# sim7600CE.net
KiCad netlist of a schematic drawn in Altium Designer
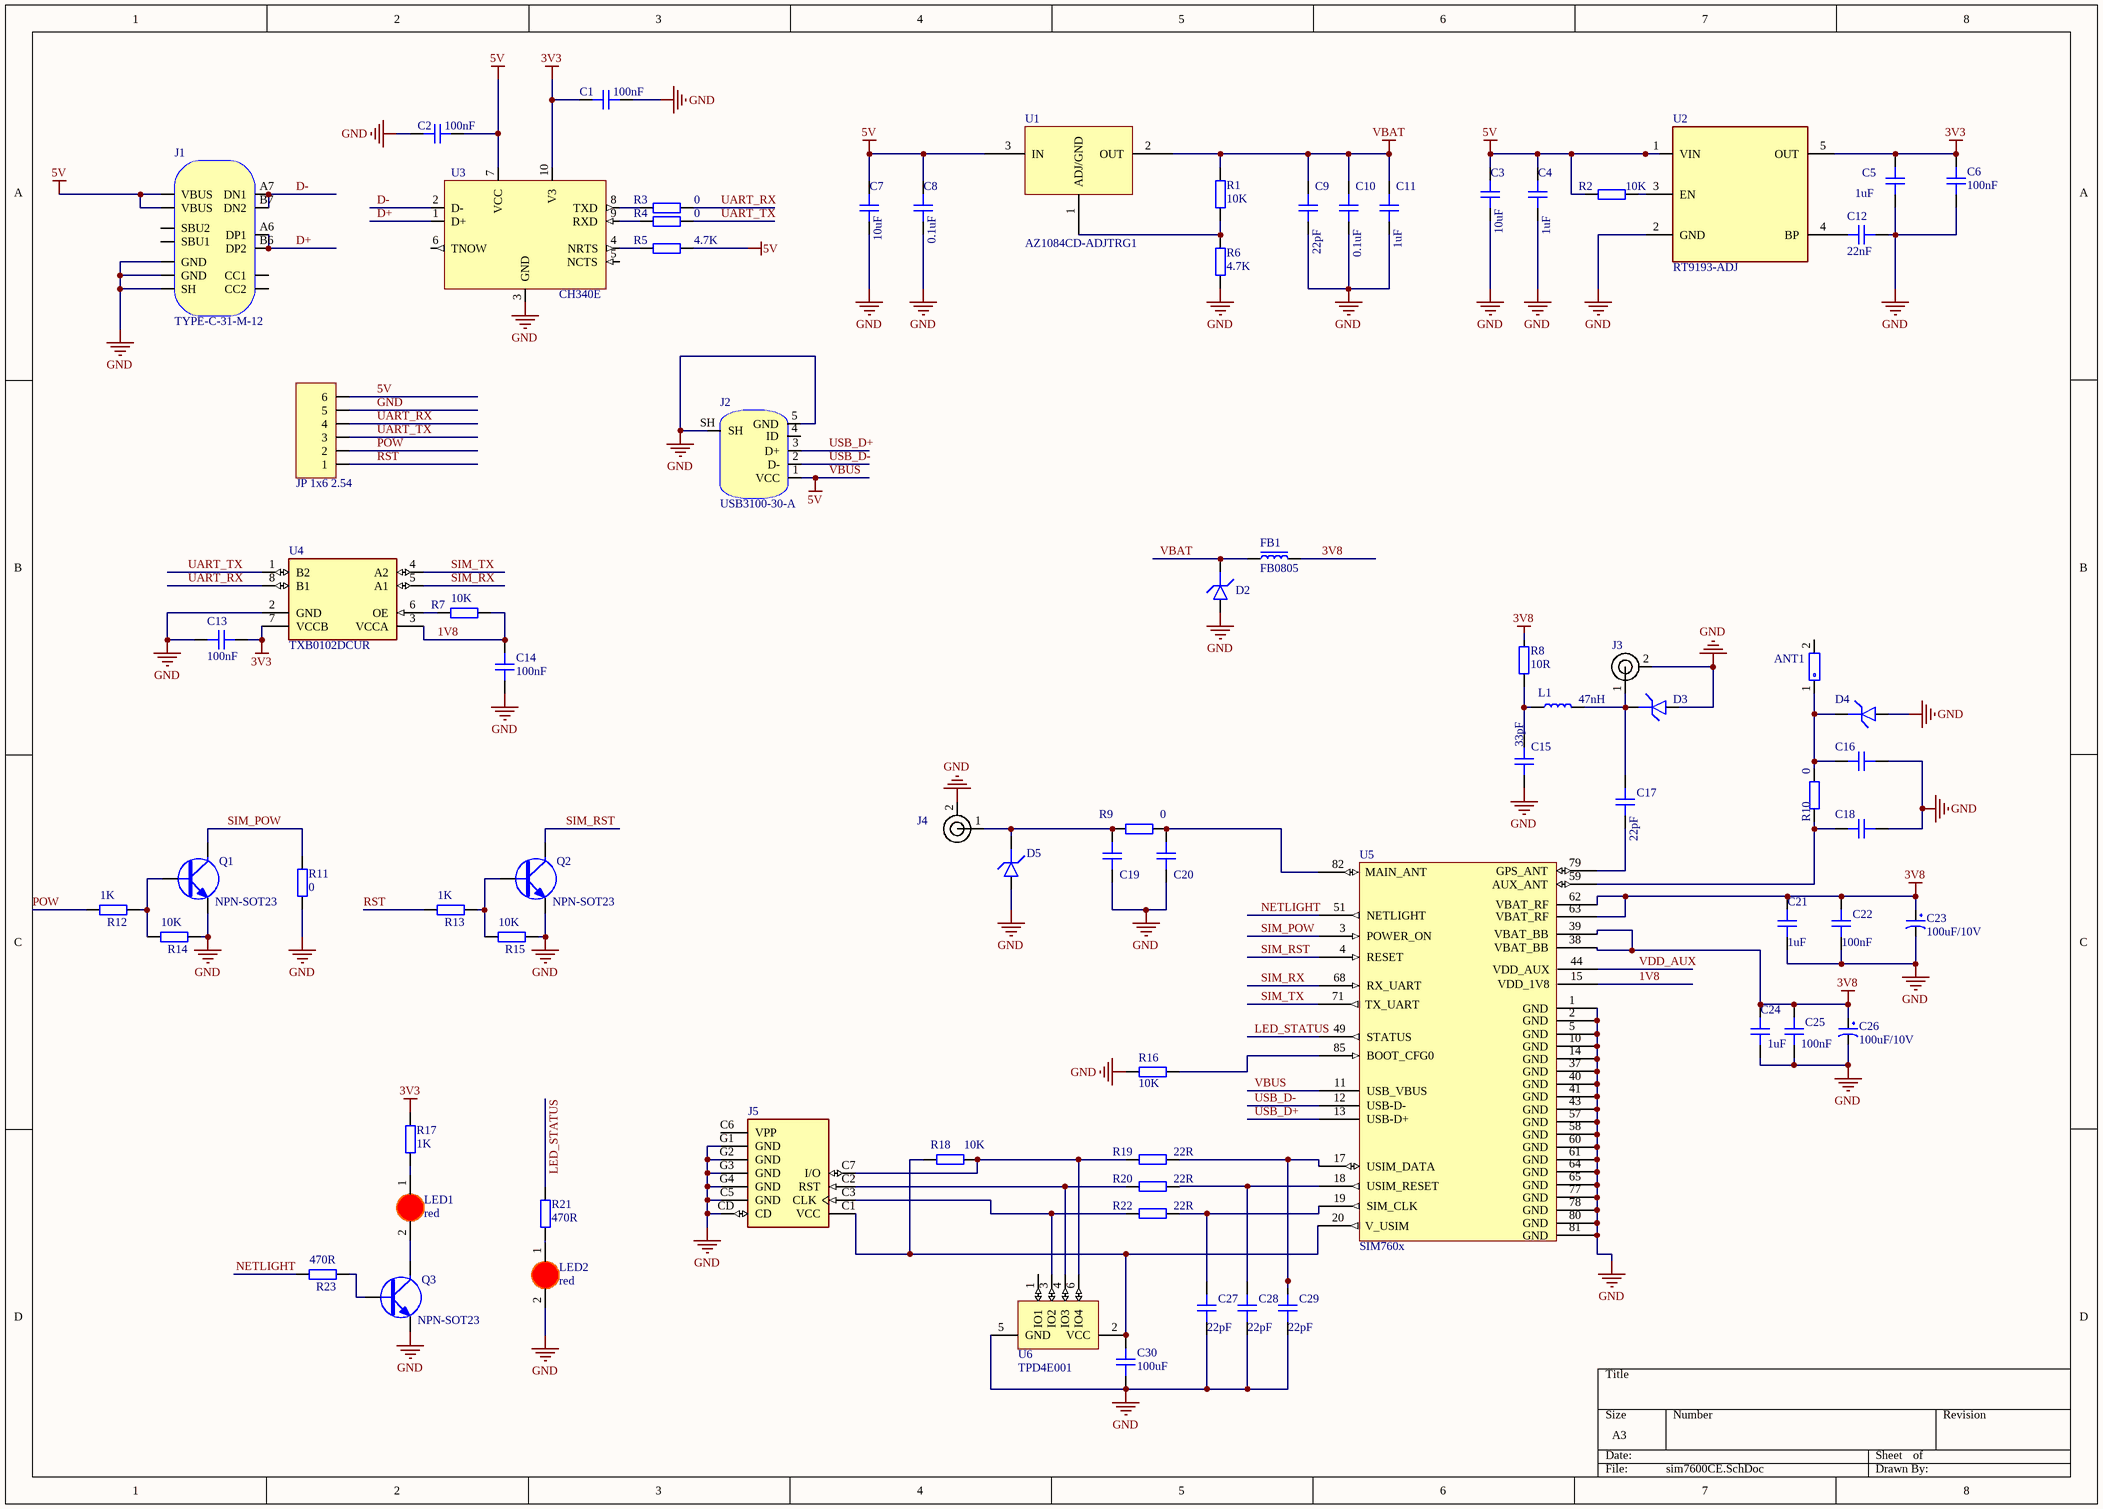
[diagram p0: sim7600CE.SchDoc]

(export (version "E")
  (design (tool "Eeschema 10.0.6"))
  (components
    (comp (ref "ANT1")
      (value "ANT MAIN")
      (footprint "AMCA92-2R660G-S1F-T")
      (libsource (lib "bethu") (part "AMCA92-2R660G-S1F-T"))
    )
    (comp (ref "C1")
      (value "100nF")
      (footprint "CAP_0603")
      (description "Capacitor SMD 0603")
      (libsource (lib "bethu") (part "CAP_0603"))
    )
    (comp (ref "C2")
      (value "100nF")
      (footprint "CAP_0603")
      (description "Capacitor SMD 0603")
      (libsource (lib "bethu") (part "CAP_0603"))
    )
    (comp (ref "C3")
      (value "10uF")
      (footprint "CAP_0603")
      (description "Capacitor SMD 0603")
      (libsource (lib "bethu") (part "CAP_0603"))
    )
    (comp (ref "C4")
      (value "1uF")
      (footprint "CAP_0603")
      (description "Capacitor SMD 0603")
      (libsource (lib "bethu") (part "CAP_0603"))
    )
    (comp (ref "C5")
      (value "1uF")
      (footprint "CAP_0603")
      (description "Capacitor SMD 0603")
      (libsource (lib "bethu") (part "CAP_0603"))
    )
    (comp (ref "C6")
      (value "100nF")
      (footprint "CAP_0603")
      (description "Capacitor SMD 0603")
      (libsource (lib "bethu") (part "CAP_0603"))
    )
    (comp (ref "C7")
      (value "10uF")
      (footprint "CAP_0603")
      (description "Capacitor SMD 0603")
      (libsource (lib "bethu") (part "CAP_0603"))
    )
    (comp (ref "C8")
      (value "0.1uF")
      (footprint "CAP_0603")
      (description "Capacitor SMD 0603")
      (libsource (lib "bethu") (part "CAP_0603"))
    )
    (comp (ref "C9")
      (value "22pF")
      (footprint "CAP_0603")
      (description "Capacitor SMD 0603")
      (libsource (lib "bethu") (part "CAP_0603"))
    )
    (comp (ref "C10")
      (value "0.1uF")
      (footprint "CAP_0603")
      (description "Capacitor SMD 0603")
      (libsource (lib "bethu") (part "CAP_0603"))
    )
    (comp (ref "C11")
      (value "1uF")
      (footprint "CAP_0603")
      (description "Capacitor SMD 0603")
      (libsource (lib "bethu") (part "CAP_0603"))
    )
    (comp (ref "C12")
      (value "22nF")
      (footprint "CAP_0603")
      (description "Capacitor SMD 0603")
      (libsource (lib "bethu") (part "CAP_0603"))
    )
    (comp (ref "C13")
      (value "100nF")
      (footprint "CAP_0603")
      (description "Capacitor SMD 0603")
      (libsource (lib "bethu") (part "CAP_0603"))
    )
    (comp (ref "C14")
      (value "100nF")
      (footprint "CAP_0603")
      (description "Capacitor SMD 0603")
      (libsource (lib "bethu") (part "CAP_0603"))
    )
    (comp (ref "C15")
      (value "33pF")
      (footprint "CAP_0603")
      (description "Capacitor SMD 0603")
      (libsource (lib "bethu") (part "CAP_0603"))
    )
    (comp (ref "C16")
      (value "C0603")
      (footprint "CAP_0603")
      (description "Capacitor SMD 0603")
      (libsource (lib "bethu") (part "CAP_0603"))
    )
    (comp (ref "C17")
      (value "22pF")
      (footprint "CAP_0603")
      (description "Capacitor SMD 0603")
      (libsource (lib "bethu") (part "CAP_0603"))
    )
    (comp (ref "C18")
      (value "C0603")
      (footprint "CAP_0603")
      (description "Capacitor SMD 0603")
      (libsource (lib "bethu") (part "CAP_0603"))
    )
    (comp (ref "C19")
      (value "C0603")
      (footprint "CAP_0603")
      (description "Capacitor SMD 0603")
      (libsource (lib "bethu") (part "CAP_0603"))
    )
    (comp (ref "C20")
      (value "C0603")
      (footprint "CAP_0603")
      (description "Capacitor SMD 0603")
      (libsource (lib "bethu") (part "CAP_0603"))
    )
    (comp (ref "C21")
      (value "1uF")
      (footprint "CAP_0603")
      (description "Capacitor SMD 0603")
      (libsource (lib "bethu") (part "CAP_0603"))
    )
    (comp (ref "C22")
      (value "100nF")
      (footprint "CAP_0603")
      (description "Capacitor SMD 0603")
      (libsource (lib "bethu") (part "CAP_0603"))
    )
    (comp (ref "C23")
      (value "100uF/10V")
      (footprint "tu tantalum smd3216")
      (description "Tụ tantalum 7343 477C 16V 470uF 7.3x4.3mm")
      (libsource (lib "bethu") (part "CAP 477C"))
    )
    (comp (ref "C24")
      (value "1uF")
      (footprint "CAP_0603")
      (description "Capacitor SMD 0603")
      (libsource (lib "bethu") (part "CAP_0603"))
    )
    (comp (ref "C25")
      (value "100nF")
      (footprint "CAP_0603")
      (description "Capacitor SMD 0603")
      (libsource (lib "bethu") (part "CAP_0603"))
    )
    (comp (ref "C26")
      (value "100uF/10V")
      (footprint "tu tantalum smd3216")
      (description "Tụ tantalum 7343 477C 16V 470uF 7.3x4.3mm")
      (libsource (lib "bethu") (part "CAP 477C"))
    )
    (comp (ref "C27")
      (value "22pF")
      (footprint "CAP_0603")
      (description "Capacitor SMD 0603")
      (libsource (lib "bethu") (part "CAP_0603"))
    )
    (comp (ref "C28")
      (value "22pF")
      (footprint "CAP_0603")
      (description "Capacitor SMD 0603")
      (libsource (lib "bethu") (part "CAP_0603"))
    )
    (comp (ref "C29")
      (value "22pF")
      (footprint "CAP_0603")
      (description "Capacitor SMD 0603")
      (libsource (lib "bethu") (part "CAP_0603"))
    )
    (comp (ref "C30")
      (value "100uF")
      (footprint "CAP_0603")
      (description "Capacitor SMD 0603")
      (libsource (lib "bethu") (part "CAP_0603"))
    )
    (comp (ref "D2")
      (value "D_TVS_0402")
      (footprint "D_0402")
      (description "Diode TVS / ESD 0402")
      (libsource (lib "bethu") (part "D_TVS_0402"))
    )
    (comp (ref "D3")
      (value "D_TVS_0402")
      (footprint "D_0402")
      (description "Diode TVS / ESD 0402")
      (libsource (lib "bethu") (part "D_TVS_0402"))
    )
    (comp (ref "D4")
      (value "D_TVS_0402")
      (footprint "D_0402")
      (description "Diode TVS / ESD 0402")
      (libsource (lib "bethu") (part "D_TVS_0402"))
    )
    (comp (ref "D5")
      (value "D_TVS_0402")
      (footprint "D_0402")
      (description "Diode TVS / ESD 0402")
      (libsource (lib "bethu") (part "D_TVS_0402"))
    )
    (comp (ref "FB1")
      (value "FB0805")
      (footprint "FB_0805")
      (description "Ferrite Bead SMD 0805")
      (libsource (lib "bethu") (part "FB_0805"))
    )
    (comp (ref "J1")
      (value "TYPE-C-31-M-12")
      (footprint "TYPE-C-31-M-12")
      (description "USB Type C Connector Horizontal SMT")
      (fields (field (name "MANUFACTURER") "Koren Hroparts"))
      (libsource (lib "bethu") (part "TYPE-C-31-M-12"))
    )
    (comp (ref "J2")
      (value "USB3100-30-A")
      (footprint "USB3100-30-A")
      (description "USB Connector Type Micro B 2.0 SMD Reverse Mount")
      (fields (field (name "MANUFACTURER") "GCT"))
      (libsource (lib "bethu") (part "USB3100-30-A"))
    )
    (comp (ref "J3")
      (value "U.FL-R-SMT-1(60)")
      (footprint "U.FL-R-SMT-1(60)")
      (description "RF Connector u.FL 50 Ohms 6 GHz")
      (fields (field (name "MANUFACTURER") "Hirose Connector"))
      (libsource (lib "bethu") (part "ANT-SMD"))
    )
    (comp (ref "J4")
      (value "U.FL-R-SMT-1(60)")
      (footprint "U.FL-R-SMT-1(60)")
      (description "RF Connector u.FL 50 Ohms 6 GHz")
      (fields (field (name "MANUFACTURER") "Hirose Connector"))
      (libsource (lib "bethu") (part "ANT-SMD"))
    )
    (comp (ref "J5")
      (value "SIM8066-6-1-14-01-A_REVA")
      (footprint "GCT_SIM8066-6-1-14-01-A_REVA")
      (description "Nano SIM Card ConnectorPush-Push Type, SMT, 6Pin, 1.44mm Profile")
      (libsource (lib "bethu") (part "SIM8066-6-1-14-01-A_REVA"))
    )
    (comp (ref "JP1")
      (value "JP 1x6 2.54")
      (footprint "HDR1X6")
      (description "Cắm")
      (libsource (lib "bethu") (part "JP 1x6 2.54 Duc Thang"))
    )
    (comp (ref "L1")
      (value "47nH")
      (footprint "IND_0603")
      (description "Inductor SMD 0603")
      (libsource (lib "bethu") (part "IND_0603"))
    )
    (comp (ref "LED1")
      (value "red")
      (footprint "LED-0805-Red")
      (libsource (lib "bethu") (part "LED_0805_RED"))
    )
    (comp (ref "LED2")
      (value "red")
      (footprint "LED-0805-Red")
      (libsource (lib "bethu") (part "LED_0805_RED"))
    )
    (comp (ref "Q1")
      (value "NPN-SOT23")
      (footprint "SOT23 - 3PIN")
      (libsource (lib "bethu") (part "NPN-SOT23"))
    )
    (comp (ref "Q2")
      (value "NPN-SOT23")
      (footprint "SOT23 - 3PIN")
      (libsource (lib "bethu") (part "NPN-SOT23"))
    )
    (comp (ref "Q3")
      (value "NPN-SOT23")
      (footprint "SOT23 - 3PIN")
      (libsource (lib "bethu") (part "NPN-SOT23"))
    )
    (comp (ref "R1")
      (value "10K")
      (footprint "RES_0603")
      (description "Resistor SMD 0603")
      (libsource (lib "bethu") (part "RES_0603"))
    )
    (comp (ref "R2")
      (value "10K")
      (footprint "RES_0603")
      (description "Resistor SMD 0603")
      (libsource (lib "bethu") (part "RES_0603"))
    )
    (comp (ref "R3")
      (value "0")
      (footprint "RES_0603")
      (description "Resistor SMD 0603")
      (libsource (lib "bethu") (part "RES_0603"))
    )
    (comp (ref "R4")
      (value "0")
      (footprint "RES_0603")
      (description "Resistor SMD 0603")
      (libsource (lib "bethu") (part "RES_0603"))
    )
    (comp (ref "R5")
      (value "4.7K")
      (footprint "RES_0603")
      (description "Resistor SMD 0603")
      (libsource (lib "bethu") (part "RES_0603"))
    )
    (comp (ref "R6")
      (value "4.7K")
      (footprint "RES_0603")
      (description "Resistor SMD 0603")
      (libsource (lib "bethu") (part "RES_0603"))
    )
    (comp (ref "R7")
      (value "10K")
      (footprint "RES_0603")
      (description "Resistor SMD 0603")
      (libsource (lib "bethu") (part "RES_0603"))
    )
    (comp (ref "R8")
      (value "10R")
      (footprint "RES_0603")
      (description "Resistor SMD 0603")
      (libsource (lib "bethu") (part "RES_0603"))
    )
    (comp (ref "R9")
      (value "0")
      (footprint "RES_0603")
      (description "Resistor SMD 0603")
      (libsource (lib "bethu") (part "RES_0603"))
    )
    (comp (ref "R10")
      (value "0")
      (footprint "RES_0603")
      (description "Resistor SMD 0603")
      (libsource (lib "bethu") (part "RES_0603"))
    )
    (comp (ref "R11")
      (value "0")
      (footprint "RES_0603")
      (description "Resistor SMD 0603")
      (libsource (lib "bethu") (part "RES_0603"))
    )
    (comp (ref "R12")
      (value "1K")
      (footprint "RES_0603")
      (description "Resistor SMD 0603")
      (libsource (lib "bethu") (part "RES_0603"))
    )
    (comp (ref "R13")
      (value "1K")
      (footprint "RES_0603")
      (description "Resistor SMD 0603")
      (libsource (lib "bethu") (part "RES_0603"))
    )
    (comp (ref "R14")
      (value "10K")
      (footprint "RES_0603")
      (description "Resistor SMD 0603")
      (libsource (lib "bethu") (part "RES_0603"))
    )
    (comp (ref "R15")
      (value "10K")
      (footprint "RES_0603")
      (description "Resistor SMD 0603")
      (libsource (lib "bethu") (part "RES_0603"))
    )
    (comp (ref "R16")
      (value "10K")
      (footprint "RES_0603")
      (description "Resistor SMD 0603")
      (libsource (lib "bethu") (part "RES_0603"))
    )
    (comp (ref "R17")
      (value "1K")
      (footprint "RES_0603")
      (description "Resistor SMD 0603")
      (libsource (lib "bethu") (part "RES_0603"))
    )
    (comp (ref "R18")
      (value "10K")
      (footprint "RES_0603")
      (description "Resistor SMD 0603")
      (libsource (lib "bethu") (part "RES_0603"))
    )
    (comp (ref "R19")
      (value "22R")
      (footprint "RES_0603")
      (description "Resistor SMD 0603")
      (libsource (lib "bethu") (part "RES_0603"))
    )
    (comp (ref "R20")
      (value "22R")
      (footprint "RES_0603")
      (description "Resistor SMD 0603")
      (libsource (lib "bethu") (part "RES_0603"))
    )
    (comp (ref "R21")
      (value "470R")
      (footprint "RES_0603")
      (description "Resistor SMD 0603")
      (libsource (lib "bethu") (part "RES_0603"))
    )
    (comp (ref "R22")
      (value "22R")
      (footprint "RES_0603")
      (description "Resistor SMD 0603")
      (libsource (lib "bethu") (part "RES_0603"))
    )
    (comp (ref "R23")
      (value "470R")
      (footprint "RES_0603")
      (description "Resistor SMD 0603")
      (libsource (lib "bethu") (part "RES_0603"))
    )
    (comp (ref "U1")
      (value "AZ1084CD-ADJTRG1")
      (footprint "TO252 DPAK")
      (description "Linear Voltage Regulator IC Positive Adjustable 1 Output 5A TO-252-3")
      (libsource (lib "bethu") (part "AZ1084CD-ADJTRG1"))
    )
    (comp (ref "U2")
      (value "RT9193-ADJ")
      (footprint "SOT-23-5")
      (description "Linear Voltage Regulator IC Positive Fixed 1 Output 300mA SOT-23-5")
      (libsource (lib "bethu") (part "RT9193"))
    )
    (comp (ref "U3")
      (value "CH340E")
      (footprint "MSOP-10")
      (description "USB-to-UART Transceiver MSOP-10")
      (libsource (lib "bethu") (part "CH340E"))
    )
    (comp (ref "U4")
      (value "TXB0102DCUR")
      (footprint "txb0102")
      (fields (field (name "DIGI-KEY_PART_NUMBER") "296-22862-1-ND") (field (name "MF") "Texas Instruments"))
      (libsource (lib "bethu") (part "TXB0102DCUR"))
    )
    (comp (ref "U5")
      (value "SIM760x")
      (footprint "SIM7600CE - duplicate")
      (libsource (lib "bethu") (part "SIM760x"))
    )
    (comp (ref "U6") (value "TPD4E001") (footprint "TSOT-26-6") (libsource (lib "bethu") (part "TPD4E001")))
  )
  (nets
    (net (code "1") (name "/1V8") (class "Default")
      (node (ref "C14") (pin "1") (pinfunction "1_1") (pintype "passive"))
      (node (ref "R7") (pin "2") (pinfunction "2_2") (pintype "passive"))
      (node (ref "U4") (pin "3") (pinfunction "VCCA_3") (pintype "power_in"))
      (node (ref "U5") (pin "15") (pinfunction "VDD_1V8_15") (pintype "passive"))
    )
    (net (code "2") (name "/D+") (class "Default")
      (node (ref "J1") (pin "A6") (pinfunction "DP1_A6") (pintype "bidirectional"))
      (node (ref "J1") (pin "B6") (pinfunction "DP2_B6") (pintype "bidirectional"))
      (node (ref "U3") (pin "1") (pinfunction "D+_1") (pintype "bidirectional"))
    )
    (net (code "3") (name "/D-") (class "Default")
      (node (ref "J1") (pin "A7") (pinfunction "DN1_A7") (pintype "bidirectional"))
      (node (ref "J1") (pin "B7") (pinfunction "DN2_B7") (pintype "bidirectional"))
      (node (ref "U3") (pin "2") (pinfunction "D-_2") (pintype "bidirectional"))
    )
    (net (code "4") (name "/LED_STATUS") (class "Default")
      (node (ref "R21") (pin "1") (pinfunction "1_1") (pintype "passive"))
      (node (ref "U5") (pin "49") (pinfunction "STATUS_49") (pintype "output"))
    )
    (net (code "5") (name "/NETLIGHT") (class "Default")
      (node (ref "R23") (pin "1") (pinfunction "1_1") (pintype "passive"))
      (node (ref "U5") (pin "51") (pinfunction "NETLIGHT_51") (pintype "output"))
    )
    (net (code "6") (name "/POW") (class "Default")
      (node (ref "JP1") (pin "2") (pinfunction "2_2") (pintype "passive"))
      (node (ref "R12") (pin "1") (pinfunction "1_1") (pintype "passive"))
    )
    (net (code "7") (name "/RST") (class "Default")
      (node (ref "JP1") (pin "1") (pinfunction "1_1") (pintype "passive"))
      (node (ref "R13") (pin "1") (pinfunction "1_1") (pintype "passive"))
    )
    (net (code "8") (name "/SIM_POW") (class "Default")
      (node (ref "Q1") (pin "3") (pinfunction "C_3") (pintype "passive"))
      (node (ref "R11") (pin "2") (pinfunction "2_2") (pintype "passive"))
      (node (ref "U5") (pin "3") (pinfunction "POWER_ON_3") (pintype "input"))
    )
    (net (code "9") (name "/SIM_RST") (class "Default")
      (node (ref "Q2") (pin "3") (pinfunction "C_3") (pintype "passive"))
      (node (ref "U5") (pin "4") (pinfunction "RESET_4") (pintype "input"))
    )
    (net (code "10") (name "/SIM_RX") (class "Default")
      (node (ref "U4") (pin "5") (pinfunction "A1_5") (pintype "bidirectional"))
      (node (ref "U5") (pin "68") (pinfunction "RX_UART_68") (pintype "input"))
    )
    (net (code "11") (name "/SIM_TX") (class "Default")
      (node (ref "U4") (pin "4") (pinfunction "A2_4") (pintype "bidirectional"))
      (node (ref "U5") (pin "71") (pinfunction "TX_UART_71") (pintype "output"))
    )
    (net (code "12") (name "/UART_RX") (class "Default")
      (node (ref "JP1") (pin "4") (pinfunction "4_4") (pintype "passive"))
      (node (ref "R3") (pin "2") (pinfunction "2_2") (pintype "passive"))
      (node (ref "U4") (pin "8") (pinfunction "B1_8") (pintype "bidirectional"))
    )
    (net (code "13") (name "/UART_TX") (class "Default")
      (node (ref "JP1") (pin "3") (pinfunction "3_3") (pintype "passive"))
      (node (ref "R4") (pin "2") (pinfunction "2_2") (pintype "passive"))
      (node (ref "U4") (pin "1") (pinfunction "B2_1") (pintype "bidirectional"))
    )
    (net (code "14") (name "/USB_D+") (class "Default")
      (node (ref "J2") (pin "3") (pinfunction "D+_3") (pintype "passive"))
      (node (ref "U5") (pin "13") (pinfunction "USB-D+_13") (pintype "passive"))
    )
    (net (code "15") (name "/USB_D-") (class "Default")
      (node (ref "J2") (pin "2") (pinfunction "D-_2") (pintype "passive"))
      (node (ref "U5") (pin "12") (pinfunction "USB-D-_12") (pintype "passive"))
    )
    (net (code "16") (name "/VDD_AUX") (class "Default")
      (node (ref "U5") (pin "44") (pinfunction "VDD_AUX_44") (pintype "passive"))
    )
    (net (code "17") (name "3V3") (class "Default")
      (node (ref "C1") (pin "1") (pinfunction "1_1") (pintype "passive"))
      (node (ref "C13") (pin "2") (pinfunction "2_2") (pintype "passive"))
      (node (ref "C5") (pin "1") (pinfunction "1_1") (pintype "passive"))
      (node (ref "C6") (pin "1") (pinfunction "1_1") (pintype "passive"))
      (node (ref "R17") (pin "2") (pinfunction "2_2") (pintype "passive"))
      (node (ref "U2") (pin "5") (pinfunction "OUT_5") (pintype "passive"))
      (node (ref "U3") (pin "10") (pinfunction "V3_10") (pintype "power_in"))
      (node (ref "U4") (pin "7") (pinfunction "VCCB_7") (pintype "power_in"))
    )
    (net (code "18") (name "3V8") (class "Default")
      (node (ref "C21") (pin "1") (pinfunction "1_1") (pintype "passive"))
      (node (ref "C22") (pin "1") (pinfunction "1_1") (pintype "passive"))
      (node (ref "C23") (pin "1") (pinfunction "1_1") (pintype "passive"))
      (node (ref "C24") (pin "1") (pinfunction "1_1") (pintype "passive"))
      (node (ref "C25") (pin "1") (pinfunction "1_1") (pintype "passive"))
      (node (ref "C26") (pin "1") (pinfunction "1_1") (pintype "passive"))
      (node (ref "FB1") (pin "2") (pinfunction "2_2") (pintype "passive"))
      (node (ref "R8") (pin "2") (pinfunction "2_2") (pintype "passive"))
      (node (ref "U5") (pin "38") (pinfunction "VBAT_BB_38") (pintype "passive"))
      (node (ref "U5") (pin "39") (pinfunction "VBAT_BB_39") (pintype "passive"))
      (node (ref "U5") (pin "62") (pinfunction "VBAT_RF_62") (pintype "passive"))
      (node (ref "U5") (pin "63") (pinfunction "VBAT_RF_63") (pintype "passive"))
    )
    (net (code "19") (name "5V") (class "Default")
      (node (ref "C2") (pin "2") (pinfunction "2_2") (pintype "passive"))
      (node (ref "C3") (pin "1") (pinfunction "1_1") (pintype "passive"))
      (node (ref "C4") (pin "1") (pinfunction "1_1") (pintype "passive"))
      (node (ref "C7") (pin "1") (pinfunction "1_1") (pintype "passive"))
      (node (ref "C8") (pin "1") (pinfunction "1_1") (pintype "passive"))
      (node (ref "J1") (pin "A4B9") (pinfunction "VBUS_A4B9") (pintype "power_in"))
      (node (ref "J1") (pin "B4A9") (pinfunction "VBUS_B4A9") (pintype "power_in"))
      (node (ref "J2") (pin "1") (pinfunction "VCC_1") (pintype "passive"))
      (node (ref "JP1") (pin "6") (pinfunction "6_6") (pintype "passive"))
      (node (ref "R2") (pin "1") (pinfunction "1_1") (pintype "passive"))
      (node (ref "R5") (pin "2") (pinfunction "2_2") (pintype "passive"))
      (node (ref "U1") (pin "3") (pinfunction "IN_3") (pintype "passive"))
      (node (ref "U2") (pin "1") (pinfunction "VIN_1") (pintype "passive"))
      (node (ref "U3") (pin "7") (pinfunction "VCC_7") (pintype "power_in"))
      (node (ref "U5") (pin "11") (pinfunction "USB_VBUS_11") (pintype "passive"))
    )
    (net (code "20") (name "GND") (class "Default")
      (node (ref "C1") (pin "2") (pinfunction "2_2") (pintype "passive"))
      (node (ref "C10") (pin "2") (pinfunction "2_2") (pintype "passive"))
      (node (ref "C11") (pin "2") (pinfunction "2_2") (pintype "passive"))
      (node (ref "C12") (pin "2") (pinfunction "2_2") (pintype "passive"))
      (node (ref "C13") (pin "1") (pinfunction "1_1") (pintype "passive"))
      (node (ref "C14") (pin "2") (pinfunction "2_2") (pintype "passive"))
      (node (ref "C15") (pin "2") (pinfunction "2_2") (pintype "passive"))
      (node (ref "C16") (pin "1") (pinfunction "1_1") (pintype "passive"))
      (node (ref "C18") (pin "1") (pinfunction "1_1") (pintype "passive"))
      (node (ref "C19") (pin "1") (pinfunction "1_1") (pintype "passive"))
      (node (ref "C2") (pin "1") (pinfunction "1_1") (pintype "passive"))
      (node (ref "C20") (pin "1") (pinfunction "1_1") (pintype "passive"))
      (node (ref "C21") (pin "2") (pinfunction "2_2") (pintype "passive"))
      (node (ref "C22") (pin "2") (pinfunction "2_2") (pintype "passive"))
      (node (ref "C23") (pin "2") (pinfunction "2_2") (pintype "passive"))
      (node (ref "C24") (pin "2") (pinfunction "2_2") (pintype "passive"))
      (node (ref "C25") (pin "2") (pinfunction "2_2") (pintype "passive"))
      (node (ref "C26") (pin "2") (pinfunction "2_2") (pintype "passive"))
      (node (ref "C27") (pin "1") (pinfunction "1_1") (pintype "passive"))
      (node (ref "C28") (pin "1") (pinfunction "1_1") (pintype "passive"))
      (node (ref "C29") (pin "1") (pinfunction "1_1") (pintype "passive"))
      (node (ref "C3") (pin "2") (pinfunction "2_2") (pintype "passive"))
      (node (ref "C30") (pin "1") (pinfunction "1_1") (pintype "passive"))
      (node (ref "C4") (pin "2") (pinfunction "2_2") (pintype "passive"))
      (node (ref "C5") (pin "2") (pinfunction "2_2") (pintype "passive"))
      (node (ref "C6") (pin "2") (pinfunction "2_2") (pintype "passive"))
      (node (ref "C7") (pin "2") (pinfunction "2_2") (pintype "passive"))
      (node (ref "C8") (pin "2") (pinfunction "2_2") (pintype "passive"))
      (node (ref "C9") (pin "2") (pinfunction "2_2") (pintype "passive"))
      (node (ref "D2") (pin "A") (pinfunction "A_A") (pintype "passive"))
      (node (ref "D3") (pin "A") (pinfunction "A_A") (pintype "passive"))
      (node (ref "D4") (pin "A") (pinfunction "A_A") (pintype "passive"))
      (node (ref "D5") (pin "A") (pinfunction "A_A") (pintype "passive"))
      (node (ref "J1") (pin "A1B12") (pinfunction "GND_A1B12") (pintype "power_in"))
      (node (ref "J1") (pin "B1A12") (pinfunction "GND_B1A12") (pintype "power_in"))
      (node (ref "J1") (pin "SH") (pinfunction "SH_SH") (pintype "power_in"))
      (node (ref "J2") (pin "5") (pinfunction "GND_5") (pintype "passive"))
      (node (ref "J2") (pin "SH") (pinfunction "SH_SH") (pintype "passive"))
      (node (ref "J3") (pin "2") (pinfunction "2_2") (pintype "passive"))
      (node (ref "J4") (pin "2") (pinfunction "2_2") (pintype "passive"))
      (node (ref "J5") (pin "C5") (pinfunction "GND_C5") (pintype "power_in"))
      (node (ref "J5") (pin "CD") (pinfunction "CD_CD") (pintype "bidirectional"))
      (node (ref "J5") (pin "G1") (pinfunction "GND_G1") (pintype "power_in"))
      (node (ref "J5") (pin "G2") (pinfunction "GND_G2") (pintype "power_in"))
      (node (ref "J5") (pin "G3") (pinfunction "GND_G3") (pintype "power_in"))
      (node (ref "J5") (pin "G4") (pinfunction "GND_G4") (pintype "power_in"))
      (node (ref "JP1") (pin "5") (pinfunction "5_5") (pintype "passive"))
      (node (ref "LED2") (pin "2") (pinfunction "K_2") (pintype "passive"))
      (node (ref "Q1") (pin "2") (pinfunction "E_2") (pintype "passive"))
      (node (ref "Q2") (pin "2") (pinfunction "E_2") (pintype "passive"))
      (node (ref "Q3") (pin "2") (pinfunction "E_2") (pintype "passive"))
      (node (ref "R11") (pin "1") (pinfunction "1_1") (pintype "passive"))
      (node (ref "R14") (pin "2") (pinfunction "2_2") (pintype "passive"))
      (node (ref "R15") (pin "2") (pinfunction "2_2") (pintype "passive"))
      (node (ref "R16") (pin "1") (pinfunction "1_1") (pintype "passive"))
      (node (ref "R6") (pin "1") (pinfunction "1_1") (pintype "passive"))
      (node (ref "U2") (pin "2") (pinfunction "GND_2") (pintype "passive"))
      (node (ref "U3") (pin "3") (pinfunction "GND_3") (pintype "power_in"))
      (node (ref "U4") (pin "2") (pinfunction "GND_2") (pintype "power_in"))
      (node (ref "U5") (pin "1") (pinfunction "GND_1") (pintype "passive"))
      (node (ref "U5") (pin "10") (pinfunction "GND_10") (pintype "passive"))
      (node (ref "U5") (pin "14") (pinfunction "GND_14") (pintype "passive"))
      (node (ref "U5") (pin "2") (pinfunction "GND_2") (pintype "passive"))
      (node (ref "U5") (pin "37") (pinfunction "GND_37") (pintype "passive"))
      (node (ref "U5") (pin "40") (pinfunction "GND_40") (pintype "passive"))
      (node (ref "U5") (pin "41") (pinfunction "GND_41") (pintype "passive"))
      (node (ref "U5") (pin "43") (pinfunction "GND_43") (pintype "passive"))
      (node (ref "U5") (pin "5") (pinfunction "GND_5") (pintype "passive"))
      (node (ref "U5") (pin "57") (pinfunction "GND_57") (pintype "passive"))
      (node (ref "U5") (pin "58") (pinfunction "GND_58") (pintype "passive"))
      (node (ref "U5") (pin "60") (pinfunction "GND_60") (pintype "passive"))
      (node (ref "U5") (pin "61") (pinfunction "GND_61") (pintype "passive"))
      (node (ref "U5") (pin "64") (pinfunction "GND_64") (pintype "passive"))
      (node (ref "U5") (pin "65") (pinfunction "GND_65") (pintype "passive"))
      (node (ref "U5") (pin "77") (pinfunction "GND_77") (pintype "passive"))
      (node (ref "U5") (pin "78") (pinfunction "GND_78") (pintype "passive"))
      (node (ref "U5") (pin "80") (pinfunction "GND_80") (pintype "passive"))
      (node (ref "U5") (pin "81") (pinfunction "GND_81") (pintype "passive"))
      (node (ref "U6") (pin "5") (pinfunction "GND_5") (pintype "passive"))
    )
    (net (code "21") (name "Net-(ANT1-Pad1)") (class "Default")
      (node (ref "ANT1") (pin "1") (pinfunction "1_1") (pintype "passive"))
      (node (ref "C16") (pin "2") (pinfunction "2_2") (pintype "passive"))
      (node (ref "D4") (pin "K") (pinfunction "K_K") (pintype "passive"))
      (node (ref "R10") (pin "1") (pinfunction "1_1") (pintype "passive"))
    )
    (net (code "22") (name "Net-(C15-Pad1)") (class "Default")
      (node (ref "C15") (pin "1") (pinfunction "1_1") (pintype "passive"))
      (node (ref "L1") (pin "1") (pinfunction "1_1") (pintype "passive"))
      (node (ref "R8") (pin "1") (pinfunction "1_1") (pintype "passive"))
    )
    (net (code "23") (name "Net-(C17-Pad2)") (class "Default")
      (node (ref "C17") (pin "2") (pinfunction "2_2") (pintype "passive"))
      (node (ref "D3") (pin "K") (pinfunction "K_K") (pintype "passive"))
      (node (ref "J3") (pin "1") (pinfunction "1_1") (pintype "passive"))
      (node (ref "L1") (pin "2") (pinfunction "2_2") (pintype "passive"))
    )
    (net (code "24") (name "Net-(C19-Pad2)") (class "Default")
      (node (ref "C19") (pin "2") (pinfunction "2_2") (pintype "passive"))
      (node (ref "D5") (pin "K") (pinfunction "K_K") (pintype "passive"))
      (node (ref "J4") (pin "1") (pinfunction "1_1") (pintype "passive"))
      (node (ref "R9") (pin "2") (pinfunction "2_2") (pintype "passive"))
    )
    (net (code "25") (name "Net-(J5-CLK)") (class "Default")
      (node (ref "J5") (pin "C3") (pinfunction "CLK_C3") (pintype "input"))
      (node (ref "R22") (pin "1") (pinfunction "1_1") (pintype "passive"))
      (node (ref "U6") (pin "3") (pinfunction "IO2_3") (pintype "bidirectional"))
    )
    (net (code "26") (name "Net-(J5-I{slash}O)") (class "Default")
      (node (ref "J5") (pin "C7") (pinfunction "I/O_C7") (pintype "bidirectional"))
      (node (ref "R18") (pin "2") (pinfunction "2_2") (pintype "passive"))
      (node (ref "R19") (pin "1") (pinfunction "1_1") (pintype "passive"))
      (node (ref "U6") (pin "6") (pinfunction "IO4_6") (pintype "bidirectional"))
    )
    (net (code "27") (name "Net-(J5-RST)") (class "Default")
      (node (ref "J5") (pin "C2") (pinfunction "RST_C2") (pintype "input"))
      (node (ref "R20") (pin "1") (pinfunction "1_1") (pintype "passive"))
      (node (ref "U6") (pin "4") (pinfunction "IO3_4") (pintype "bidirectional"))
    )
    (net (code "28") (name "Net-(J5-VCC)") (class "Default")
      (node (ref "C30") (pin "2") (pinfunction "2_2") (pintype "passive"))
      (node (ref "J5") (pin "C1") (pinfunction "VCC_C1") (pintype "power_in"))
      (node (ref "R18") (pin "1") (pinfunction "1_1") (pintype "passive"))
      (node (ref "U5") (pin "20") (pinfunction "V_USIM_20") (pintype "output"))
      (node (ref "U6") (pin "2") (pinfunction "VCC_2") (pintype "passive"))
    )
    (net (code "29") (name "Net-(LED1-A)") (class "Default")
      (node (ref "LED1") (pin "1") (pinfunction "A_1") (pintype "passive"))
      (node (ref "R17") (pin "1") (pinfunction "1_1") (pintype "passive"))
    )
    (net (code "30") (name "Net-(LED1-K)") (class "Default")
      (node (ref "LED1") (pin "2") (pinfunction "K_2") (pintype "passive"))
      (node (ref "Q3") (pin "3") (pinfunction "C_3") (pintype "passive"))
    )
    (net (code "31") (name "Net-(LED2-A)") (class "Default")
      (node (ref "LED2") (pin "1") (pinfunction "A_1") (pintype "passive"))
      (node (ref "R21") (pin "2") (pinfunction "2_2") (pintype "passive"))
    )
    (net (code "32") (name "Net-(Q1-B)") (class "Default")
      (node (ref "Q1") (pin "1") (pinfunction "B_1") (pintype "passive"))
      (node (ref "R12") (pin "2") (pinfunction "2_2") (pintype "passive"))
      (node (ref "R14") (pin "1") (pinfunction "1_1") (pintype "passive"))
    )
    (net (code "33") (name "Net-(Q2-B)") (class "Default")
      (node (ref "Q2") (pin "1") (pinfunction "B_1") (pintype "passive"))
      (node (ref "R13") (pin "2") (pinfunction "2_2") (pintype "passive"))
      (node (ref "R15") (pin "1") (pinfunction "1_1") (pintype "passive"))
    )
    (net (code "34") (name "Net-(Q3-B)") (class "Default")
      (node (ref "Q3") (pin "1") (pinfunction "B_1") (pintype "passive"))
      (node (ref "R23") (pin "2") (pinfunction "2_2") (pintype "passive"))
    )
    (net (code "35") (name "Net-(U1-ADJ{slash}GND)") (class "Default")
      (node (ref "R1") (pin "1") (pinfunction "1_1") (pintype "passive"))
      (node (ref "R6") (pin "2") (pinfunction "2_2") (pintype "passive"))
      (node (ref "U1") (pin "1") (pinfunction "ADJ/GND_1") (pintype "passive"))
    )
    (net (code "36") (name "Net-(U2-BP)") (class "Default")
      (node (ref "C12") (pin "1") (pinfunction "1_1") (pintype "passive"))
      (node (ref "U2") (pin "4") (pinfunction "BP_4") (pintype "passive"))
    )
    (net (code "37") (name "Net-(U2-EN)") (class "Default")
      (node (ref "R2") (pin "2") (pinfunction "2_2") (pintype "passive"))
      (node (ref "U2") (pin "3") (pinfunction "EN_3") (pintype "passive"))
    )
    (net (code "38") (name "Net-(U3-NRTS)") (class "Default")
      (node (ref "R5") (pin "1") (pinfunction "1_1") (pintype "passive"))
      (node (ref "U3") (pin "4") (pinfunction "NRTS_4") (pintype "output"))
    )
    (net (code "39") (name "Net-(U3-RXD)") (class "Default")
      (node (ref "R4") (pin "1") (pinfunction "1_1") (pintype "passive"))
      (node (ref "U3") (pin "9") (pinfunction "RXD_9") (pintype "input"))
    )
    (net (code "40") (name "Net-(U3-TXD)") (class "Default")
      (node (ref "R3") (pin "1") (pinfunction "1_1") (pintype "passive"))
      (node (ref "U3") (pin "8") (pinfunction "TXD_8") (pintype "output"))
    )
    (net (code "41") (name "Net-(U4-OE)") (class "Default")
      (node (ref "R7") (pin "1") (pinfunction "1_1") (pintype "passive"))
      (node (ref "U4") (pin "6") (pinfunction "OE_6") (pintype "input"))
    )
    (net (code "42") (name "Net-(U5-AUX_ANT)") (class "Default")
      (node (ref "C18") (pin "2") (pinfunction "2_2") (pintype "passive"))
      (node (ref "R10") (pin "2") (pinfunction "2_2") (pintype "passive"))
      (node (ref "U5") (pin "59") (pinfunction "AUX_ANT_59") (pintype "bidirectional"))
    )
    (net (code "43") (name "Net-(U5-BOOT_CFG0)") (class "Default")
      (node (ref "R16") (pin "2") (pinfunction "2_2") (pintype "passive"))
      (node (ref "U5") (pin "85") (pinfunction "BOOT_CFG0_85") (pintype "input"))
    )
    (net (code "44") (name "Net-(U5-GPS_ANT)") (class "Default")
      (node (ref "C17") (pin "1") (pinfunction "1_1") (pintype "passive"))
      (node (ref "U5") (pin "79") (pinfunction "GPS_ANT_79") (pintype "bidirectional"))
    )
    (net (code "45") (name "Net-(U5-MAIN_ANT)") (class "Default")
      (node (ref "C20") (pin "2") (pinfunction "2_2") (pintype "passive"))
      (node (ref "R9") (pin "1") (pinfunction "1_1") (pintype "passive"))
      (node (ref "U5") (pin "82") (pinfunction "MAIN_ANT_82") (pintype "bidirectional"))
    )
    (net (code "46") (name "Net-(U5-SIM_CLK)") (class "Default")
      (node (ref "C27") (pin "2") (pinfunction "2_2") (pintype "passive"))
      (node (ref "R22") (pin "2") (pinfunction "2_2") (pintype "passive"))
      (node (ref "U5") (pin "19") (pinfunction "SIM_CLK_19") (pintype "output"))
    )
    (net (code "47") (name "Net-(U5-USIM_DATA)") (class "Default")
      (node (ref "C29") (pin "2") (pinfunction "2_2") (pintype "passive"))
      (node (ref "R19") (pin "2") (pinfunction "2_2") (pintype "passive"))
      (node (ref "U5") (pin "17") (pinfunction "USIM_DATA_17") (pintype "bidirectional"))
    )
    (net (code "48") (name "Net-(U5-USIM_RESET)") (class "Default")
      (node (ref "C28") (pin "2") (pinfunction "2_2") (pintype "passive"))
      (node (ref "R20") (pin "2") (pinfunction "2_2") (pintype "passive"))
      (node (ref "U5") (pin "18") (pinfunction "USIM_RESET_18") (pintype "output"))
    )
    (net (code "49") (name "VBAT") (class "Default")
      (node (ref "C10") (pin "1") (pinfunction "1_1") (pintype "passive"))
      (node (ref "C11") (pin "1") (pinfunction "1_1") (pintype "passive"))
      (node (ref "C9") (pin "1") (pinfunction "1_1") (pintype "passive"))
      (node (ref "D2") (pin "K") (pinfunction "K_K") (pintype "passive"))
      (node (ref "FB1") (pin "1") (pinfunction "1_1") (pintype "passive"))
      (node (ref "R1") (pin "2") (pinfunction "2_2") (pintype "passive"))
      (node (ref "U1") (pin "2") (pinfunction "OUT_2") (pintype "passive"))
    )
    (net (code "50") (name "unconnected-(ANT1-Pad2)") (class "Default")
      (node (ref "ANT1") (pin "2") (pinfunction "2_2") (pintype "passive"))
    )
    (net (code "51") (name "unconnected-(J1-CC1-PadA5)") (class "Default")
      (node (ref "J1") (pin "A5") (pinfunction "CC1_A5") (pintype "passive"))
    )
    (net (code "52") (name "unconnected-(J1-CC2-PadB5)") (class "Default")
      (node (ref "J1") (pin "B5") (pinfunction "CC2_B5") (pintype "tri_state"))
    )
    (net (code "53") (name "unconnected-(J1-SBU1-PadA8)") (class "Default")
      (node (ref "J1") (pin "A8") (pinfunction "SBU1_A8") (pintype "bidirectional"))
    )
    (net (code "54") (name "unconnected-(J1-SBU2-PadB8)") (class "Default")
      (node (ref "J1") (pin "B8") (pinfunction "SBU2_B8") (pintype "bidirectional"))
    )
    (net (code "55") (name "unconnected-(J2-ID-Pad4)") (class "Default")
      (node (ref "J2") (pin "4") (pinfunction "ID_4") (pintype "passive"))
    )
    (net (code "56") (name "unconnected-(J5-VPP-PadC6)") (class "Default")
      (node (ref "J5") (pin "C6") (pinfunction "VPP_C6") (pintype "power_in"))
    )
    (net (code "57") (name "unconnected-(U3-NCTS-Pad5)") (class "Default")
      (node (ref "U3") (pin "5") (pinfunction "NCTS_5") (pintype "input"))
    )
    (net (code "58") (name "unconnected-(U3-TNOW-Pad6)") (class "Default")
      (node (ref "U3") (pin "6") (pinfunction "TNOW_6") (pintype "output"))
    )
    (net (code "59") (name "unconnected-(U6-IO1-Pad1)") (class "Default")
      (node (ref "U6") (pin "1") (pinfunction "IO1_1") (pintype "bidirectional"))
    )
  )
)
